# EEG.net
KiCad netlist of a schematic drawn in Altium Designer
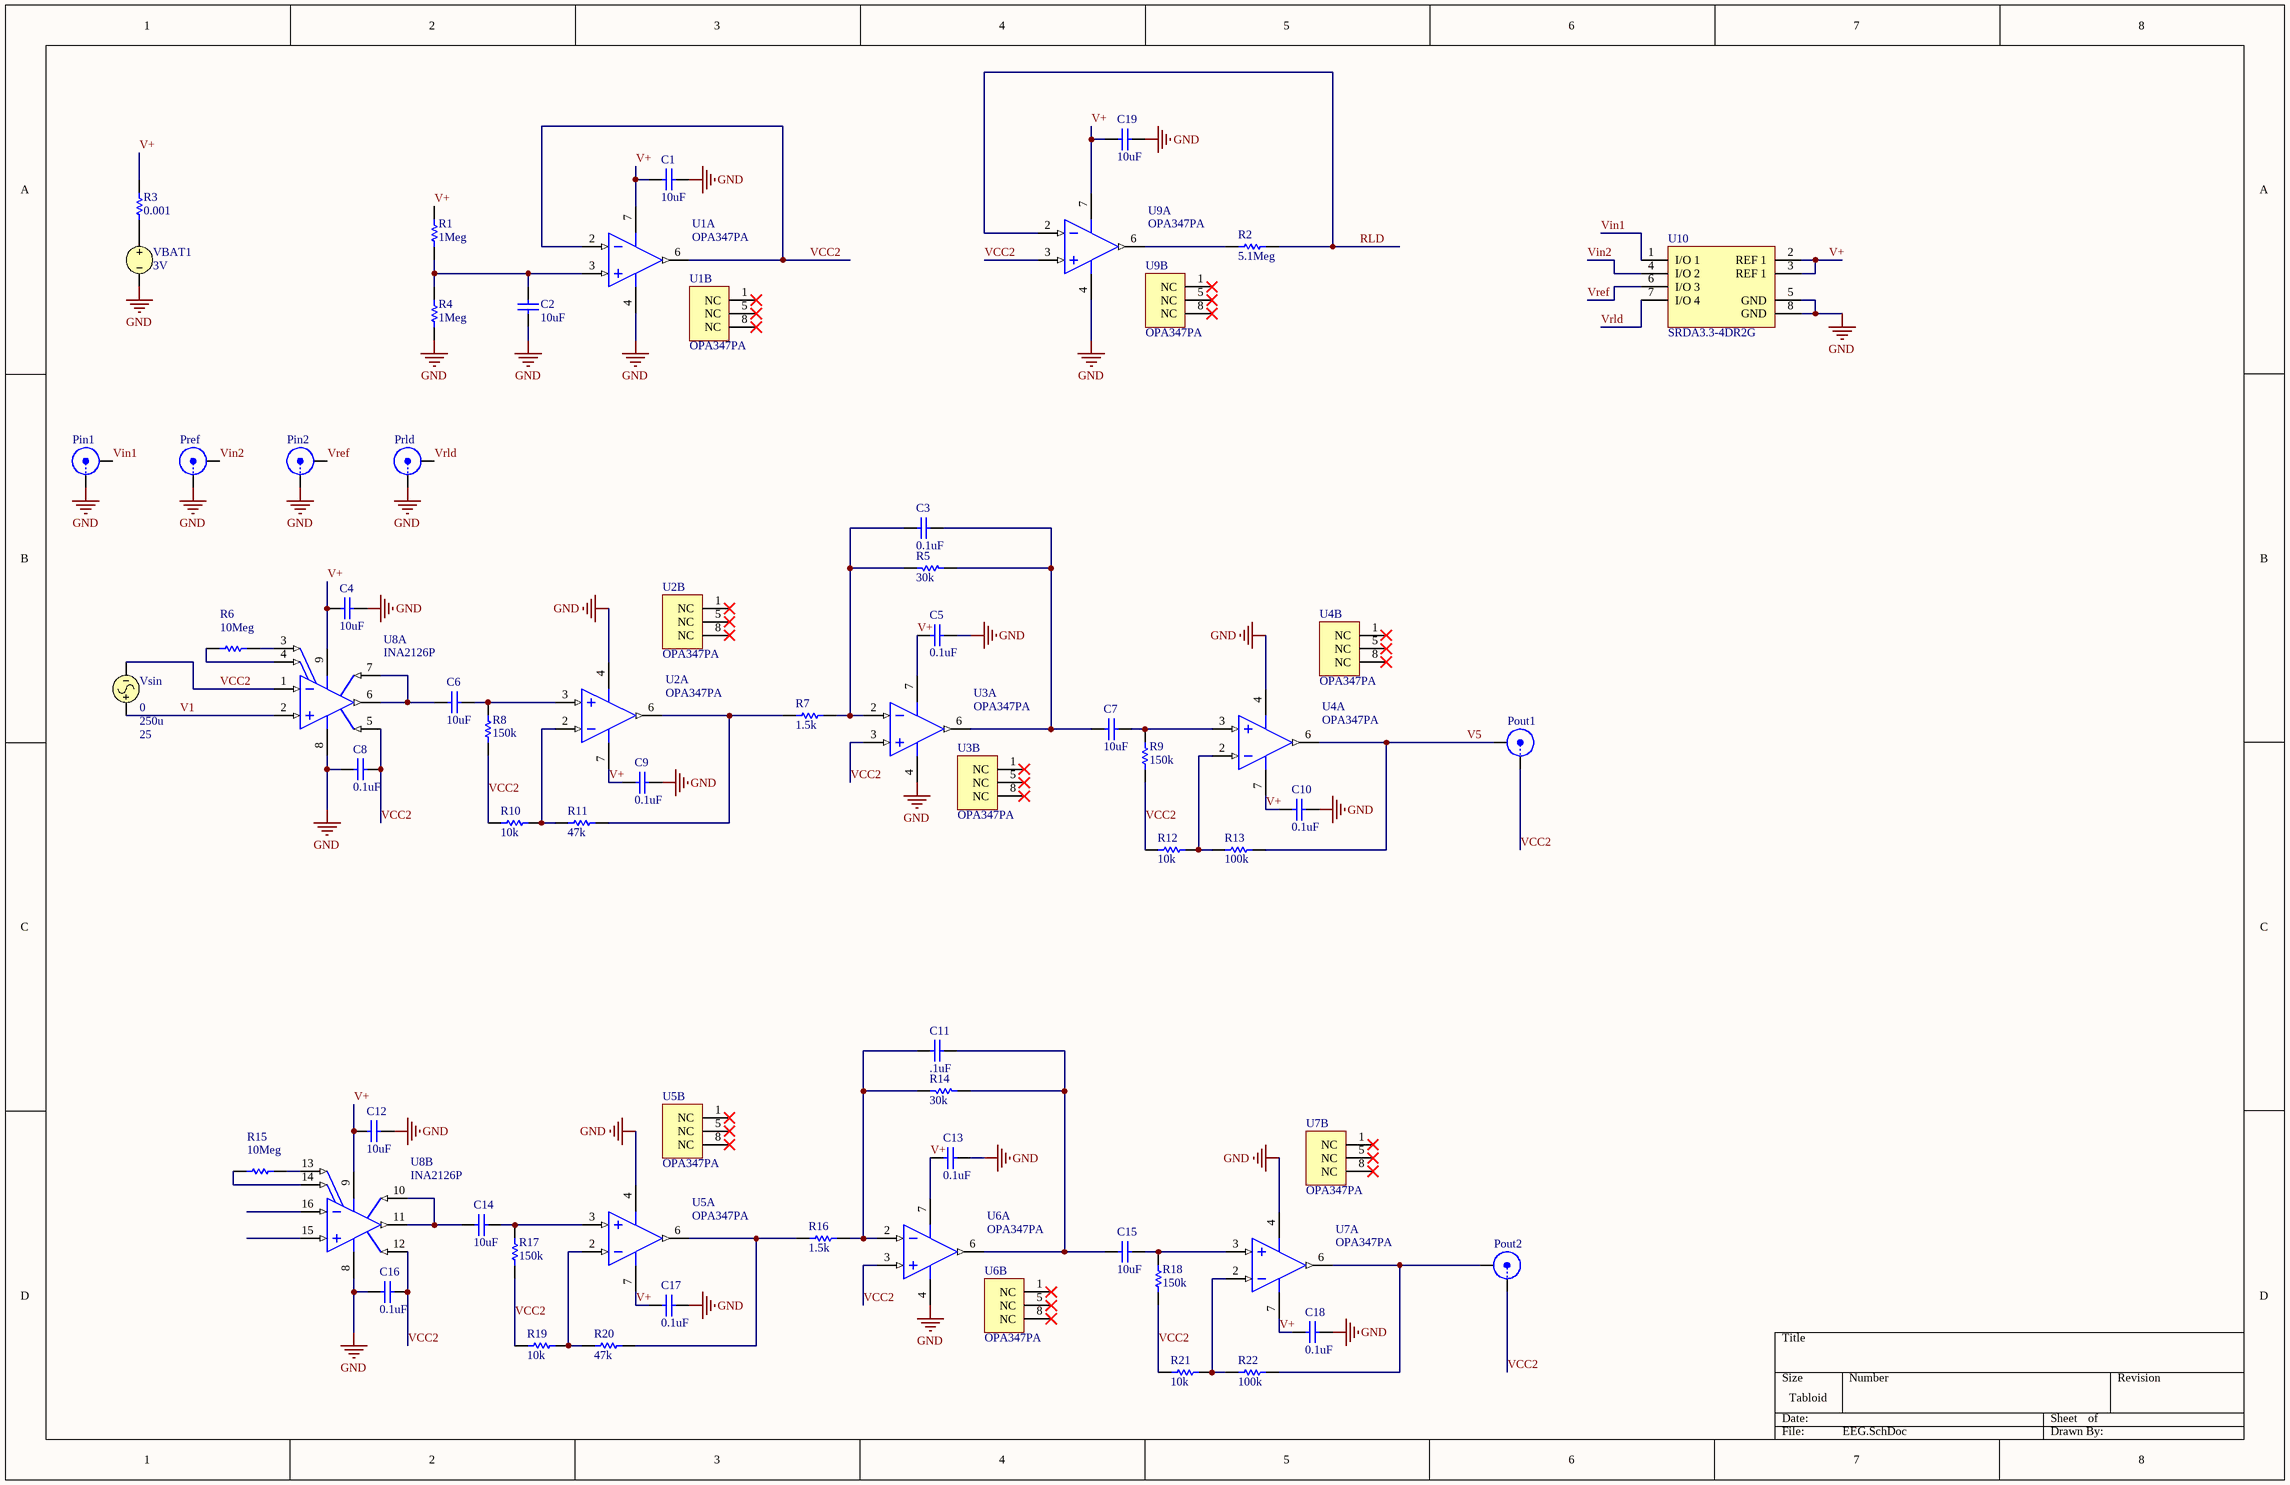
[diagram p0: EEG.SchDoc]

(export (version "E")
  (design (tool "Eeschema 10.0.6"))
  (components
    (comp (ref "C1")
      (value "10uF")
      (footprint "Miscellaneous Devices:RAD-0.2")
      (description "Capacitor")
      (fields (field (name "PUBLISHER") "Altium Limited"))
      (libsource (lib "Miscellaneous Devices") (part "Cap"))
    )
    (comp (ref "C2")
      (value "10uF")
      (footprint "Miscellaneous Devices:RAD-0.2")
      (description "Capacitor")
      (fields (field (name "PUBLISHER") "Altium Limited"))
      (libsource (lib "Miscellaneous Devices") (part "Cap"))
    )
    (comp (ref "C3")
      (value "0.1uF")
      (footprint "Miscellaneous Devices:RAD-0.2")
      (description "Capacitor")
      (fields (field (name "PUBLISHER") "Altium Limited"))
      (libsource (lib "Miscellaneous Devices") (part "Cap"))
    )
    (comp (ref "C4")
      (value "10uF")
      (footprint "Miscellaneous Devices:RAD-0.2")
      (description "Capacitor")
      (fields (field (name "PUBLISHER") "Altium Limited"))
      (libsource (lib "Miscellaneous Devices") (part "Cap"))
    )
    (comp (ref "C5")
      (value "0.1uF")
      (footprint "Miscellaneous Devices:RAD-0.2")
      (description "Capacitor")
      (fields (field (name "PUBLISHER") "Altium Limited"))
      (libsource (lib "Miscellaneous Devices") (part "Cap"))
    )
    (comp (ref "C6")
      (value "10uF")
      (footprint "Miscellaneous Devices:RAD-0.2")
      (description "Capacitor")
      (fields (field (name "PUBLISHER") "Altium Limited"))
      (libsource (lib "Miscellaneous Devices") (part "Cap"))
    )
    (comp (ref "C7")
      (value "10uF")
      (footprint "Miscellaneous Devices:RAD-0.2")
      (description "Capacitor")
      (fields (field (name "PUBLISHER") "Altium Limited"))
      (libsource (lib "Miscellaneous Devices") (part "Cap"))
    )
    (comp (ref "C8")
      (value "0.1uF")
      (footprint "Miscellaneous Devices:RAD-0.2")
      (description "Capacitor")
      (fields (field (name "PUBLISHER") "Altium Limited"))
      (libsource (lib "Miscellaneous Devices") (part "Cap"))
    )
    (comp (ref "C9")
      (value "0.1uF")
      (footprint "Miscellaneous Devices:RAD-0.2")
      (description "Capacitor")
      (fields (field (name "PUBLISHER") "Altium Limited"))
      (libsource (lib "Miscellaneous Devices") (part "Cap"))
    )
    (comp (ref "C10")
      (value "0.1uF")
      (footprint "Miscellaneous Devices:RAD-0.2")
      (description "Capacitor")
      (fields (field (name "PUBLISHER") "Altium Limited"))
      (libsource (lib "Miscellaneous Devices") (part "Cap"))
    )
    (comp (ref "C11")
      (value ".1uF")
      (footprint "Miscellaneous Devices:RAD-0.2")
      (description "Capacitor")
      (fields (field (name "PUBLISHER") "Altium Limited"))
      (libsource (lib "Miscellaneous Devices") (part "Cap"))
    )
    (comp (ref "C12")
      (value "10uF")
      (footprint "Miscellaneous Devices:RAD-0.2")
      (description "Capacitor")
      (fields (field (name "PUBLISHER") "Altium Limited"))
      (libsource (lib "Miscellaneous Devices") (part "Cap"))
    )
    (comp (ref "C13")
      (value "0.1uF")
      (footprint "Miscellaneous Devices:RAD-0.2")
      (description "Capacitor")
      (fields (field (name "PUBLISHER") "Altium Limited"))
      (libsource (lib "Miscellaneous Devices") (part "Cap"))
    )
    (comp (ref "C14")
      (value "10uF")
      (footprint "Miscellaneous Devices:RAD-0.2")
      (description "Capacitor")
      (fields (field (name "PUBLISHER") "Altium Limited"))
      (libsource (lib "Miscellaneous Devices") (part "Cap"))
    )
    (comp (ref "C15")
      (value "10uF")
      (footprint "Miscellaneous Devices:RAD-0.2")
      (description "Capacitor")
      (fields (field (name "PUBLISHER") "Altium Limited"))
      (libsource (lib "Miscellaneous Devices") (part "Cap"))
    )
    (comp (ref "C16")
      (value "0.1uF")
      (footprint "Miscellaneous Devices:RAD-0.2")
      (description "Capacitor")
      (fields (field (name "PUBLISHER") "Altium Limited"))
      (libsource (lib "Miscellaneous Devices") (part "Cap"))
    )
    (comp (ref "C17")
      (value "0.1uF")
      (footprint "Miscellaneous Devices:RAD-0.2")
      (description "Capacitor")
      (fields (field (name "PUBLISHER") "Altium Limited"))
      (libsource (lib "Miscellaneous Devices") (part "Cap"))
    )
    (comp (ref "C18")
      (value "0.1uF")
      (footprint "Miscellaneous Devices:RAD-0.2")
      (description "Capacitor")
      (fields (field (name "PUBLISHER") "Altium Limited"))
      (libsource (lib "Miscellaneous Devices") (part "Cap"))
    )
    (comp (ref "C19")
      (value "10uF")
      (footprint "Miscellaneous Devices:RAD-0.2")
      (description "Capacitor")
      (fields (field (name "PUBLISHER") "Altium Limited"))
      (libsource (lib "Miscellaneous Devices") (part "Cap"))
    )
    (comp (ref "Pin1")
      (value "BNC")
      (footprint "BNC_RA CON")
      (description "BNC Elbow Connector")
      (fields (field (name "PUBLISHER") "Altium Limited"))
      (libsource (lib "Miscellaneous Connectors") (part "BNC"))
    )
    (comp (ref "Pin2")
      (value "BNC")
      (footprint "BNC_RA CON")
      (description "BNC Elbow Connector")
      (fields (field (name "PUBLISHER") "Altium Limited"))
      (libsource (lib "Miscellaneous Connectors") (part "BNC"))
    )
    (comp (ref "Pout1")
      (value "BNC")
      (footprint "BNC_RA CON")
      (description "BNC Elbow Connector")
      (fields (field (name "PUBLISHER") "Altium Limited"))
      (libsource (lib "Miscellaneous Connectors") (part "BNC"))
    )
    (comp (ref "Pout2")
      (value "BNC")
      (footprint "BNC_RA CON")
      (description "BNC Elbow Connector")
      (fields (field (name "PUBLISHER") "Altium Limited"))
      (libsource (lib "Miscellaneous Connectors") (part "BNC"))
    )
    (comp (ref "Pref")
      (value "BNC")
      (footprint "BNC_RA CON")
      (description "BNC Elbow Connector")
      (fields (field (name "PUBLISHER") "Altium Limited"))
      (libsource (lib "Miscellaneous Connectors") (part "BNC"))
    )
    (comp (ref "Prld")
      (value "BNC")
      (footprint "BNC_RA CON")
      (description "BNC Elbow Connector")
      (fields (field (name "PUBLISHER") "Altium Limited"))
      (libsource (lib "Miscellaneous Connectors") (part "BNC"))
    )
    (comp (ref "R1")
      (value "1Meg")
      (footprint "AXIAL-0.3")
      (description "Resistor")
      (fields (field (name "PUBLISHER") "Altium Limited"))
      (libsource (lib "Miscellaneous Devices") (part "Res1"))
    )
    (comp (ref "R2")
      (value "5.1Meg")
      (footprint "AXIAL-0.3")
      (description "Resistor")
      (fields (field (name "PUBLISHER") "Altium Limited"))
      (libsource (lib "Miscellaneous Devices") (part "Res1"))
    )
    (comp (ref "R3")
      (value "0.001")
      (footprint "AXIAL-0.3")
      (description "Resistor")
      (fields (field (name "PUBLISHER") "Altium Limited"))
      (libsource (lib "Miscellaneous Devices") (part "Res1"))
    )
    (comp (ref "R4")
      (value "1Meg")
      (footprint "AXIAL-0.3")
      (description "Resistor")
      (fields (field (name "PUBLISHER") "Altium Limited"))
      (libsource (lib "Miscellaneous Devices") (part "Res1"))
    )
    (comp (ref "R5")
      (value "30k")
      (footprint "AXIAL-0.3")
      (description "Resistor")
      (fields (field (name "PUBLISHER") "Altium Limited"))
      (libsource (lib "Miscellaneous Devices") (part "Res1"))
    )
    (comp (ref "R6")
      (value "10Meg")
      (footprint "AXIAL-0.3")
      (description "Resistor")
      (fields (field (name "PUBLISHER") "Altium Limited"))
      (libsource (lib "Miscellaneous Devices") (part "Res1"))
    )
    (comp (ref "R7")
      (value "1.5k")
      (footprint "AXIAL-0.3")
      (description "Resistor")
      (fields (field (name "PUBLISHER") "Altium Limited"))
      (libsource (lib "Miscellaneous Devices") (part "Res1"))
    )
    (comp (ref "R8")
      (value "150k")
      (footprint "AXIAL-0.3")
      (description "Resistor")
      (fields (field (name "PUBLISHER") "Altium Limited"))
      (libsource (lib "Miscellaneous Devices") (part "Res1"))
    )
    (comp (ref "R9")
      (value "150k")
      (footprint "AXIAL-0.3")
      (description "Resistor")
      (fields (field (name "PUBLISHER") "Altium Limited"))
      (libsource (lib "Miscellaneous Devices") (part "Res1"))
    )
    (comp (ref "R10")
      (value "10k")
      (footprint "AXIAL-0.3")
      (description "Resistor")
      (fields (field (name "PUBLISHER") "Altium Limited"))
      (libsource (lib "Miscellaneous Devices") (part "Res1"))
    )
    (comp (ref "R11")
      (value "47k")
      (footprint "AXIAL-0.3")
      (description "Resistor")
      (fields (field (name "PUBLISHER") "Altium Limited"))
      (libsource (lib "Miscellaneous Devices") (part "Res1"))
    )
    (comp (ref "R12")
      (value "10k")
      (footprint "AXIAL-0.3")
      (description "Resistor")
      (fields (field (name "PUBLISHER") "Altium Limited"))
      (libsource (lib "Miscellaneous Devices") (part "Res1"))
    )
    (comp (ref "R13")
      (value "100k")
      (footprint "AXIAL-0.3")
      (description "Resistor")
      (fields (field (name "PUBLISHER") "Altium Limited"))
      (libsource (lib "Miscellaneous Devices") (part "Res1"))
    )
    (comp (ref "R14")
      (value "30k")
      (footprint "AXIAL-0.3")
      (description "Resistor")
      (fields (field (name "PUBLISHER") "Altium Limited"))
      (libsource (lib "Miscellaneous Devices") (part "Res1"))
    )
    (comp (ref "R15")
      (value "10Meg")
      (footprint "AXIAL-0.3")
      (description "Resistor")
      (fields (field (name "PUBLISHER") "Altium Limited"))
      (libsource (lib "Miscellaneous Devices") (part "Res1"))
    )
    (comp (ref "R16")
      (value "1.5k")
      (footprint "AXIAL-0.3")
      (description "Resistor")
      (fields (field (name "PUBLISHER") "Altium Limited"))
      (libsource (lib "Miscellaneous Devices") (part "Res1"))
    )
    (comp (ref "R17")
      (value "150k")
      (footprint "AXIAL-0.3")
      (description "Resistor")
      (fields (field (name "PUBLISHER") "Altium Limited"))
      (libsource (lib "Miscellaneous Devices") (part "Res1"))
    )
    (comp (ref "R18")
      (value "150k")
      (footprint "AXIAL-0.3")
      (description "Resistor")
      (fields (field (name "PUBLISHER") "Altium Limited"))
      (libsource (lib "Miscellaneous Devices") (part "Res1"))
    )
    (comp (ref "R19")
      (value "10k")
      (footprint "AXIAL-0.3")
      (description "Resistor")
      (fields (field (name "PUBLISHER") "Altium Limited"))
      (libsource (lib "Miscellaneous Devices") (part "Res1"))
    )
    (comp (ref "R20")
      (value "47k")
      (footprint "AXIAL-0.3")
      (description "Resistor")
      (fields (field (name "PUBLISHER") "Altium Limited"))
      (libsource (lib "Miscellaneous Devices") (part "Res1"))
    )
    (comp (ref "R21")
      (value "10k")
      (footprint "AXIAL-0.3")
      (description "Resistor")
      (fields (field (name "PUBLISHER") "Altium Limited"))
      (libsource (lib "Miscellaneous Devices") (part "Res1"))
    )
    (comp (ref "R22")
      (value "100k")
      (footprint "AXIAL-0.3")
      (description "Resistor")
      (fields (field (name "PUBLISHER") "Altium Limited"))
      (libsource (lib "Miscellaneous Devices") (part "Res1"))
    )
    (comp (ref "U1")
      (value "OPA347PA")
      (footprint "TI-P8")
      (fields (field (name "MANUFACTURER") "Texas Instruments"))
      (libsource (lib "TI Amplifiers and Linear Operational Amplifier Precision Amplifier Part One") (part "OPA347PA"))
    )
    (comp (ref "U2")
      (value "OPA347PA")
      (footprint "TI-P8")
      (fields (field (name "MANUFACTURER") "Texas Instruments"))
      (libsource (lib "") (part "OPA347PA_1"))
    )
    (comp (ref "U3")
      (value "OPA347PA")
      (footprint "TI-P8")
      (fields (field (name "MANUFACTURER") "Texas Instruments"))
      (libsource (lib "TI Amplifiers and Linear Operational Amplifier Precision Amplifier Part One") (part "OPA347PA"))
    )
    (comp (ref "U4")
      (value "OPA347PA")
      (footprint "TI-P8")
      (fields (field (name "MANUFACTURER") "Texas Instruments"))
      (libsource (lib "TI Amplifiers and Linear Operational Amplifier Precision Amplifier Part One") (part "OPA347PA"))
    )
    (comp (ref "U5")
      (value "OPA347PA")
      (footprint "TI-P8")
      (fields (field (name "MANUFACTURER") "Texas Instruments"))
      (libsource (lib "TI Amplifiers and Linear Operational Amplifier Precision Amplifier Part One") (part "OPA347PA"))
    )
    (comp (ref "U6")
      (value "OPA347PA")
      (footprint "TI-P8")
      (fields (field (name "MANUFACTURER") "Texas Instruments"))
      (libsource (lib "TI Amplifiers and Linear Operational Amplifier Precision Amplifier Part One") (part "OPA347PA"))
    )
    (comp (ref "U7")
      (value "OPA347PA")
      (footprint "TI-P8")
      (fields (field (name "MANUFACTURER") "Texas Instruments"))
      (libsource (lib "TI Amplifiers and Linear Operational Amplifier Precision Amplifier Part One") (part "OPA347PA"))
    )
    (comp (ref "U8")
      (value "INA2126P")
      (footprint "TI-N16")
      (fields (field (name "MANUFACTURER") "Texas Instruments"))
      (libsource (lib "TI Amplifiers and Linear Instrumentation Amplifier") (part "INA2126P"))
    )
    (comp (ref "U9")
      (value "OPA347PA")
      (footprint "TI-P8")
      (fields (field (name "MANUFACTURER") "Texas Instruments"))
      (libsource (lib "TI Amplifiers and Linear Operational Amplifier Precision Amplifier Part One") (part "OPA347PA"))
    )
    (comp (ref "U10")
      (value "SRDA3.3-4DR2G")
      (footprint "ONSC-SOIC-8-751-07_V")
      (fields (field (name "MANUFACTURER") "On Semiconductor"))
      (libsource (lib "Altium Content Vault") (part "ONSC-NUP4106_SRDA3_3-4-SOIC-8-751-07"))
    )
    (comp (ref "VBAT1")
      (value "3V")
      (description "Voltage Source")
      (fields (field (name "PUBLISHER") "Altium Limited"))
      (libsource (lib "Simulation Sources") (part "VSRC"))
    )
    (comp (ref "Vsin")
      (value "VSIN")
      (description "Sinusoidal Voltage Source")
      (fields
        (field (name "DC MAGNITUDE") "0")
        (field (name "AMPLITUDE") "250u")
        (field (name "FREQUENCY") "25")
        (field (name "PUBLISHER") "Altium Limited")
      )
      (libsource (lib "Simulation Sources") (part "VSIN"))
    )
  )
  (nets
    (net (code "1") (name "/RLD") (class "Default")
      (node (ref "R2") (pin "1") (pinfunction "1_1") (pintype "passive"))
      (node (ref "U9") (pin "2") (pinfunction "IN-_2") (pintype "input"))
    )
    (net (code "2") (name "/V+") (class "Default")
      (node (ref "C1") (pin "2") (pinfunction "2_2") (pintype "passive"))
      (node (ref "C10") (pin "2") (pinfunction "2_2") (pintype "passive"))
      (node (ref "C12") (pin "2") (pinfunction "2_2") (pintype "passive"))
      (node (ref "C13") (pin "2") (pinfunction "2_2") (pintype "passive"))
      (node (ref "C17") (pin "2") (pinfunction "2_2") (pintype "passive"))
      (node (ref "C18") (pin "2") (pinfunction "2_2") (pintype "passive"))
      (node (ref "C19") (pin "2") (pinfunction "2_2") (pintype "passive"))
      (node (ref "C4") (pin "2") (pinfunction "2_2") (pintype "passive"))
      (node (ref "C5") (pin "2") (pinfunction "2_2") (pintype "passive"))
      (node (ref "C9") (pin "2") (pinfunction "2_2") (pintype "passive"))
      (node (ref "R1") (pin "2") (pinfunction "2_2") (pintype "passive"))
      (node (ref "R3") (pin "2") (pinfunction "2_2") (pintype "passive"))
      (node (ref "U1") (pin "7") (pinfunction "V+_7") (pintype "power_in"))
      (node (ref "U10") (pin "2") (pinfunction "REF_1_2") (pintype "passive"))
      (node (ref "U10") (pin "3") (pinfunction "REF_1_3") (pintype "passive"))
      (node (ref "U2") (pin "7") (pinfunction "V+_7") (pintype "power_in"))
      (node (ref "U3") (pin "7") (pinfunction "V+_7") (pintype "power_in"))
      (node (ref "U4") (pin "7") (pinfunction "V+_7") (pintype "power_in"))
      (node (ref "U5") (pin "7") (pinfunction "V+_7") (pintype "power_in"))
      (node (ref "U6") (pin "7") (pinfunction "V+_7") (pintype "power_in"))
      (node (ref "U7") (pin "7") (pinfunction "V+_7") (pintype "power_in"))
      (node (ref "U8") (pin "9") (pinfunction "V+_9") (pintype "power_in"))
      (node (ref "U9") (pin "7") (pinfunction "V+_7") (pintype "power_in"))
    )
    (net (code "3") (name "/V1") (class "Default")
      (node (ref "U8") (pin "2") (pinfunction "VINA+_2") (pintype "input"))
      (node (ref "Vsin") (pin "1") (pinfunction "1_1") (pintype "passive"))
    )
    (net (code "4") (name "/V5") (class "Default")
      (node (ref "Pout1") (pin "2") (pinfunction "Y_2") (pintype "passive"))
      (node (ref "R13") (pin "2") (pinfunction "2_2") (pintype "passive"))
      (node (ref "U4") (pin "6") (pinfunction "OUT_6") (pintype "output"))
    )
    (net (code "5") (name "/VCC2") (class "Default")
      (node (ref "C16") (pin "1") (pinfunction "1_1") (pintype "passive"))
      (node (ref "C8") (pin "1") (pinfunction "1_1") (pintype "passive"))
      (node (ref "Pout1") (pin "1") (pinfunction "X_1") (pintype "passive"))
      (node (ref "Pout2") (pin "1") (pinfunction "X_1") (pintype "passive"))
      (node (ref "R10") (pin "1") (pinfunction "1_1") (pintype "passive"))
      (node (ref "R12") (pin "1") (pinfunction "1_1") (pintype "passive"))
      (node (ref "R17") (pin "2") (pinfunction "2_2") (pintype "passive"))
      (node (ref "R18") (pin "2") (pinfunction "2_2") (pintype "passive"))
      (node (ref "R19") (pin "1") (pinfunction "1_1") (pintype "passive"))
      (node (ref "R21") (pin "1") (pinfunction "1_1") (pintype "passive"))
      (node (ref "R8") (pin "2") (pinfunction "2_2") (pintype "passive"))
      (node (ref "R9") (pin "2") (pinfunction "2_2") (pintype "passive"))
      (node (ref "U1") (pin "2") (pinfunction "IN-_2") (pintype "input"))
      (node (ref "U1") (pin "6") (pinfunction "OUT_6") (pintype "output"))
      (node (ref "U3") (pin "3") (pinfunction "IN+_3") (pintype "input"))
      (node (ref "U6") (pin "3") (pinfunction "IN+_3") (pintype "input"))
      (node (ref "U8") (pin "1") (pinfunction "VINA-_1") (pintype "input"))
      (node (ref "U8") (pin "12") (pinfunction "REFB_12") (pintype "input"))
      (node (ref "U8") (pin "5") (pinfunction "REFA_5") (pintype "input"))
      (node (ref "U9") (pin "3") (pinfunction "IN+_3") (pintype "input"))
      (node (ref "Vsin") (pin "2") (pinfunction "2_2") (pintype "passive"))
    )
    (net (code "6") (name "/Vin1") (class "Default")
      (node (ref "Pin1") (pin "2") (pinfunction "Y_2") (pintype "passive"))
      (node (ref "U10") (pin "1") (pinfunction "I/O_1_1") (pintype "passive"))
    )
    (net (code "7") (name "/Vin2") (class "Default")
      (node (ref "Pref") (pin "2") (pinfunction "Y_2") (pintype "passive"))
      (node (ref "U10") (pin "4") (pinfunction "I/O_2_4") (pintype "passive"))
    )
    (net (code "8") (name "/Vref") (class "Default")
      (node (ref "Pin2") (pin "2") (pinfunction "Y_2") (pintype "passive"))
      (node (ref "U10") (pin "6") (pinfunction "I/O_3_6") (pintype "passive"))
    )
    (net (code "9") (name "/Vrld") (class "Default")
      (node (ref "Prld") (pin "2") (pinfunction "Y_2") (pintype "passive"))
      (node (ref "U10") (pin "7") (pinfunction "I/O_4_7") (pintype "passive"))
    )
    (net (code "10") (name "GND") (class "Default")
      (node (ref "C1") (pin "1") (pinfunction "1_1") (pintype "passive"))
      (node (ref "C10") (pin "1") (pinfunction "1_1") (pintype "passive"))
      (node (ref "C12") (pin "1") (pinfunction "1_1") (pintype "passive"))
      (node (ref "C13") (pin "1") (pinfunction "1_1") (pintype "passive"))
      (node (ref "C16") (pin "2") (pinfunction "2_2") (pintype "passive"))
      (node (ref "C17") (pin "1") (pinfunction "1_1") (pintype "passive"))
      (node (ref "C18") (pin "1") (pinfunction "1_1") (pintype "passive"))
      (node (ref "C19") (pin "1") (pinfunction "1_1") (pintype "passive"))
      (node (ref "C2") (pin "1") (pinfunction "1_1") (pintype "passive"))
      (node (ref "C4") (pin "1") (pinfunction "1_1") (pintype "passive"))
      (node (ref "C5") (pin "1") (pinfunction "1_1") (pintype "passive"))
      (node (ref "C8") (pin "2") (pinfunction "2_2") (pintype "passive"))
      (node (ref "C9") (pin "1") (pinfunction "1_1") (pintype "passive"))
      (node (ref "Pin1") (pin "1") (pinfunction "X_1") (pintype "passive"))
      (node (ref "Pin2") (pin "1") (pinfunction "X_1") (pintype "passive"))
      (node (ref "Pref") (pin "1") (pinfunction "X_1") (pintype "passive"))
      (node (ref "Prld") (pin "1") (pinfunction "X_1") (pintype "passive"))
      (node (ref "R4") (pin "1") (pinfunction "1_1") (pintype "passive"))
      (node (ref "U1") (pin "4") (pinfunction "V-_4") (pintype "power_in"))
      (node (ref "U10") (pin "5") (pinfunction "GND_5") (pintype "power_in"))
      (node (ref "U10") (pin "8") (pinfunction "GND_8") (pintype "power_in"))
      (node (ref "U2") (pin "4") (pinfunction "V-_4") (pintype "power_in"))
      (node (ref "U3") (pin "4") (pinfunction "V-_4") (pintype "power_in"))
      (node (ref "U4") (pin "4") (pinfunction "V-_4") (pintype "power_in"))
      (node (ref "U5") (pin "4") (pinfunction "V-_4") (pintype "power_in"))
      (node (ref "U6") (pin "4") (pinfunction "V-_4") (pintype "power_in"))
      (node (ref "U7") (pin "4") (pinfunction "V-_4") (pintype "power_in"))
      (node (ref "U8") (pin "8") (pinfunction "V-_8") (pintype "power_in"))
      (node (ref "U9") (pin "4") (pinfunction "V-_4") (pintype "power_in"))
      (node (ref "VBAT1") (pin "2") (pinfunction "2_2") (pintype "passive"))
    )
    (net (code "11") (name "Net-(Pout2-Y)") (class "Default")
      (node (ref "Pout2") (pin "2") (pinfunction "Y_2") (pintype "passive"))
      (node (ref "R22") (pin "2") (pinfunction "2_2") (pintype "passive"))
      (node (ref "U7") (pin "6") (pinfunction "OUT_6") (pintype "output"))
    )
    (net (code "12") (name "Net-(R3-Pad1)") (class "Default")
      (node (ref "R3") (pin "1") (pinfunction "1_1") (pintype "passive"))
      (node (ref "VBAT1") (pin "1") (pinfunction "1_1") (pintype "passive"))
    )
    (net (code "13") (name "Net-(R6-Pad1)") (class "Default")
      (node (ref "R6") (pin "1") (pinfunction "1_1") (pintype "passive"))
      (node (ref "U8") (pin "3") (pinfunction "RGA_3") (pintype "input"))
    )
    (net (code "14") (name "Net-(R6-Pad2)") (class "Default")
      (node (ref "R6") (pin "2") (pinfunction "2_2") (pintype "passive"))
      (node (ref "U8") (pin "4") (pinfunction "RGA_4") (pintype "input"))
    )
    (net (code "15") (name "Net-(R15-Pad1)") (class "Default")
      (node (ref "R15") (pin "1") (pinfunction "1_1") (pintype "passive"))
      (node (ref "U8") (pin "13") (pinfunction "RGB_13") (pintype "input"))
    )
    (net (code "16") (name "Net-(R15-Pad2)") (class "Default")
      (node (ref "R15") (pin "2") (pinfunction "2_2") (pintype "passive"))
      (node (ref "U8") (pin "14") (pinfunction "RGB_14") (pintype "input"))
    )
    (net (code "17") (name "Net-(U1A-IN+)") (class "Default")
      (node (ref "C2") (pin "2") (pinfunction "2_2") (pintype "passive"))
      (node (ref "R1") (pin "1") (pinfunction "1_1") (pintype "passive"))
      (node (ref "R4") (pin "2") (pinfunction "2_2") (pintype "passive"))
      (node (ref "U1") (pin "3") (pinfunction "IN+_3") (pintype "input"))
    )
    (net (code "18") (name "Net-(U2A-IN+)") (class "Default")
      (node (ref "C6") (pin "1") (pinfunction "1_1") (pintype "passive"))
      (node (ref "R8") (pin "1") (pinfunction "1_1") (pintype "passive"))
      (node (ref "U2") (pin "3") (pinfunction "IN+_3") (pintype "input"))
    )
    (net (code "19") (name "Net-(U2A-IN-)") (class "Default")
      (node (ref "R10") (pin "2") (pinfunction "2_2") (pintype "passive"))
      (node (ref "R11") (pin "1") (pinfunction "1_1") (pintype "passive"))
      (node (ref "U2") (pin "2") (pinfunction "IN-_2") (pintype "input"))
    )
    (net (code "20") (name "Net-(U2A-OUT)") (class "Default")
      (node (ref "R11") (pin "2") (pinfunction "2_2") (pintype "passive"))
      (node (ref "R7") (pin "1") (pinfunction "1_1") (pintype "passive"))
      (node (ref "U2") (pin "6") (pinfunction "OUT_6") (pintype "output"))
    )
    (net (code "21") (name "Net-(U3A-IN-)") (class "Default")
      (node (ref "C3") (pin "2") (pinfunction "2_2") (pintype "passive"))
      (node (ref "R5") (pin "1") (pinfunction "1_1") (pintype "passive"))
      (node (ref "R7") (pin "2") (pinfunction "2_2") (pintype "passive"))
      (node (ref "U3") (pin "2") (pinfunction "IN-_2") (pintype "input"))
    )
    (net (code "22") (name "Net-(U3A-OUT)") (class "Default")
      (node (ref "C3") (pin "1") (pinfunction "1_1") (pintype "passive"))
      (node (ref "C7") (pin "2") (pinfunction "2_2") (pintype "passive"))
      (node (ref "R5") (pin "2") (pinfunction "2_2") (pintype "passive"))
      (node (ref "U3") (pin "6") (pinfunction "OUT_6") (pintype "output"))
    )
    (net (code "23") (name "Net-(U4A-IN+)") (class "Default")
      (node (ref "C7") (pin "1") (pinfunction "1_1") (pintype "passive"))
      (node (ref "R9") (pin "1") (pinfunction "1_1") (pintype "passive"))
      (node (ref "U4") (pin "3") (pinfunction "IN+_3") (pintype "input"))
    )
    (net (code "24") (name "Net-(U4A-IN-)") (class "Default")
      (node (ref "R12") (pin "2") (pinfunction "2_2") (pintype "passive"))
      (node (ref "R13") (pin "1") (pinfunction "1_1") (pintype "passive"))
      (node (ref "U4") (pin "2") (pinfunction "IN-_2") (pintype "input"))
    )
    (net (code "25") (name "Net-(U5A-IN+)") (class "Default")
      (node (ref "C14") (pin "1") (pinfunction "1_1") (pintype "passive"))
      (node (ref "R17") (pin "1") (pinfunction "1_1") (pintype "passive"))
      (node (ref "U5") (pin "3") (pinfunction "IN+_3") (pintype "input"))
    )
    (net (code "26") (name "Net-(U5A-IN-)") (class "Default")
      (node (ref "R19") (pin "2") (pinfunction "2_2") (pintype "passive"))
      (node (ref "R20") (pin "1") (pinfunction "1_1") (pintype "passive"))
      (node (ref "U5") (pin "2") (pinfunction "IN-_2") (pintype "input"))
    )
    (net (code "27") (name "Net-(U5A-OUT)") (class "Default")
      (node (ref "R16") (pin "1") (pinfunction "1_1") (pintype "passive"))
      (node (ref "R20") (pin "2") (pinfunction "2_2") (pintype "passive"))
      (node (ref "U5") (pin "6") (pinfunction "OUT_6") (pintype "output"))
    )
    (net (code "28") (name "Net-(U6A-IN-)") (class "Default")
      (node (ref "C11") (pin "2") (pinfunction "2_2") (pintype "passive"))
      (node (ref "R14") (pin "1") (pinfunction "1_1") (pintype "passive"))
      (node (ref "R16") (pin "2") (pinfunction "2_2") (pintype "passive"))
      (node (ref "U6") (pin "2") (pinfunction "IN-_2") (pintype "input"))
    )
    (net (code "29") (name "Net-(U6A-OUT)") (class "Default")
      (node (ref "C11") (pin "1") (pinfunction "1_1") (pintype "passive"))
      (node (ref "C15") (pin "2") (pinfunction "2_2") (pintype "passive"))
      (node (ref "R14") (pin "2") (pinfunction "2_2") (pintype "passive"))
      (node (ref "U6") (pin "6") (pinfunction "OUT_6") (pintype "output"))
    )
    (net (code "30") (name "Net-(U7A-IN+)") (class "Default")
      (node (ref "C15") (pin "1") (pinfunction "1_1") (pintype "passive"))
      (node (ref "R18") (pin "1") (pinfunction "1_1") (pintype "passive"))
      (node (ref "U7") (pin "3") (pinfunction "IN+_3") (pintype "input"))
    )
    (net (code "31") (name "Net-(U7A-IN-)") (class "Default")
      (node (ref "R21") (pin "2") (pinfunction "2_2") (pintype "passive"))
      (node (ref "R22") (pin "1") (pinfunction "1_1") (pintype "passive"))
      (node (ref "U7") (pin "2") (pinfunction "IN-_2") (pintype "input"))
    )
    (net (code "32") (name "Net-(U8A-SENSEA)") (class "Default")
      (node (ref "C6") (pin "2") (pinfunction "2_2") (pintype "passive"))
      (node (ref "U8") (pin "6") (pinfunction "VOA_6") (pintype "output"))
      (node (ref "U8") (pin "7") (pinfunction "SENSEA_7") (pintype "input"))
    )
    (net (code "33") (name "Net-(U8B-SENSEB)") (class "Default")
      (node (ref "C14") (pin "2") (pinfunction "2_2") (pintype "passive"))
      (node (ref "U8") (pin "10") (pinfunction "SENSEB_10") (pintype "input"))
      (node (ref "U8") (pin "11") (pinfunction "VOB_11") (pintype "output"))
    )
    (net (code "34") (name "Net-(U9A-OUT)") (class "Default")
      (node (ref "R2") (pin "2") (pinfunction "2_2") (pintype "passive"))
      (node (ref "U9") (pin "6") (pinfunction "OUT_6") (pintype "output"))
    )
    (net (code "35") (name "unconnected-(U1B-NC-Pad1)") (class "Default")
      (node (ref "U1") (pin "1") (pinfunction "NC_1") (pintype "passive+no_connect"))
    )
    (net (code "36") (name "unconnected-(U1B-NC-Pad5)") (class "Default")
      (node (ref "U1") (pin "5") (pinfunction "NC_5") (pintype "passive+no_connect"))
    )
    (net (code "37") (name "unconnected-(U1B-NC-Pad8)") (class "Default")
      (node (ref "U1") (pin "8") (pinfunction "NC_8") (pintype "passive+no_connect"))
    )
    (net (code "38") (name "unconnected-(U2B-NC-Pad1)") (class "Default")
      (node (ref "U2") (pin "1") (pinfunction "NC_1") (pintype "passive+no_connect"))
    )
    (net (code "39") (name "unconnected-(U2B-NC-Pad5)") (class "Default")
      (node (ref "U2") (pin "5") (pinfunction "NC_5") (pintype "passive+no_connect"))
    )
    (net (code "40") (name "unconnected-(U2B-NC-Pad8)") (class "Default")
      (node (ref "U2") (pin "8") (pinfunction "NC_8") (pintype "passive+no_connect"))
    )
    (net (code "41") (name "unconnected-(U3B-NC-Pad1)") (class "Default")
      (node (ref "U3") (pin "1") (pinfunction "NC_1") (pintype "passive+no_connect"))
    )
    (net (code "42") (name "unconnected-(U3B-NC-Pad5)") (class "Default")
      (node (ref "U3") (pin "5") (pinfunction "NC_5") (pintype "passive+no_connect"))
    )
    (net (code "43") (name "unconnected-(U3B-NC-Pad8)") (class "Default")
      (node (ref "U3") (pin "8") (pinfunction "NC_8") (pintype "passive+no_connect"))
    )
    (net (code "44") (name "unconnected-(U4B-NC-Pad1)") (class "Default")
      (node (ref "U4") (pin "1") (pinfunction "NC_1") (pintype "passive+no_connect"))
    )
    (net (code "45") (name "unconnected-(U4B-NC-Pad5)") (class "Default")
      (node (ref "U4") (pin "5") (pinfunction "NC_5") (pintype "passive+no_connect"))
    )
    (net (code "46") (name "unconnected-(U4B-NC-Pad8)") (class "Default")
      (node (ref "U4") (pin "8") (pinfunction "NC_8") (pintype "passive+no_connect"))
    )
    (net (code "47") (name "unconnected-(U5B-NC-Pad1)") (class "Default")
      (node (ref "U5") (pin "1") (pinfunction "NC_1") (pintype "passive+no_connect"))
    )
    (net (code "48") (name "unconnected-(U5B-NC-Pad5)") (class "Default")
      (node (ref "U5") (pin "5") (pinfunction "NC_5") (pintype "passive+no_connect"))
    )
    (net (code "49") (name "unconnected-(U5B-NC-Pad8)") (class "Default")
      (node (ref "U5") (pin "8") (pinfunction "NC_8") (pintype "passive+no_connect"))
    )
    (net (code "50") (name "unconnected-(U6B-NC-Pad1)") (class "Default")
      (node (ref "U6") (pin "1") (pinfunction "NC_1") (pintype "passive+no_connect"))
    )
    (net (code "51") (name "unconnected-(U6B-NC-Pad5)") (class "Default")
      (node (ref "U6") (pin "5") (pinfunction "NC_5") (pintype "passive+no_connect"))
    )
    (net (code "52") (name "unconnected-(U6B-NC-Pad8)") (class "Default")
      (node (ref "U6") (pin "8") (pinfunction "NC_8") (pintype "passive+no_connect"))
    )
    (net (code "53") (name "unconnected-(U7B-NC-Pad1)") (class "Default")
      (node (ref "U7") (pin "1") (pinfunction "NC_1") (pintype "passive+no_connect"))
    )
    (net (code "54") (name "unconnected-(U7B-NC-Pad5)") (class "Default")
      (node (ref "U7") (pin "5") (pinfunction "NC_5") (pintype "passive+no_connect"))
    )
    (net (code "55") (name "unconnected-(U7B-NC-Pad8)") (class "Default")
      (node (ref "U7") (pin "8") (pinfunction "NC_8") (pintype "passive+no_connect"))
    )
    (net (code "56") (name "unconnected-(U8B-VINB+-Pad15)") (class "Default")
      (node (ref "U8") (pin "15") (pinfunction "VINB+_15") (pintype "input"))
    )
    (net (code "57") (name "unconnected-(U8B-VINB--Pad16)") (class "Default")
      (node (ref "U8") (pin "16") (pinfunction "VINB-_16") (pintype "input"))
    )
    (net (code "58") (name "unconnected-(U9B-NC-Pad1)") (class "Default")
      (node (ref "U9") (pin "1") (pinfunction "NC_1") (pintype "passive+no_connect"))
    )
    (net (code "59") (name "unconnected-(U9B-NC-Pad5)") (class "Default")
      (node (ref "U9") (pin "5") (pinfunction "NC_5") (pintype "passive+no_connect"))
    )
    (net (code "60") (name "unconnected-(U9B-NC-Pad8)") (class "Default")
      (node (ref "U9") (pin "8") (pinfunction "NC_8") (pintype "passive+no_connect"))
    )
  )
)
